# FLASH.net
KiCad netlist of a schematic drawn in Altium Designer
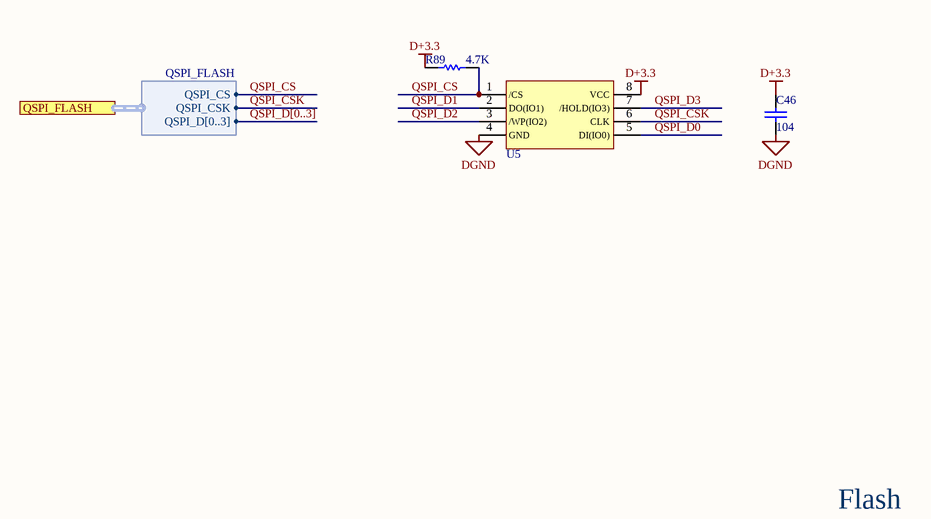
[diagram p0: FLASH.SchDoc]

(export (version "E")
  (design (tool "Eeschema 10.0.6"))
  (components
    (comp (ref "C46")
      (value "104")
      (footprint "C 0402_LL")
      (description "Capacitor")
      (fields (field (name "PUBLISHER") "Altium Limited"))
      (libsource (lib "Miscellaneous Devices") (part "Cap"))
    )
    (comp (ref "R89")
      (value "4.7K")
      (footprint "R 0603_L")
      (description "Resistor")
      (fields (field (name "PUBLISHER") "Altium Limited"))
      (libsource (lib "Miscellaneous Devices") (part "Res1"))
    )
    (comp (ref "U5")
      (value "W25Q128")
      (footprint "SOP8W_L")
      (libsource (lib "ZYNQ7010_add") (part "W25Q128"))
    )
  )
  (nets
    (net (code "2") (name "/QSPI_CS") (class "Default")
      (node (ref "R89") (pin "1") (pinfunction "1_1") (pintype "passive"))
      (node (ref "U5") (pin "1") (pinfunction "/CS_1") (pintype "passive"))
    )
    (net (code "3") (name "/QSPI_CSK") (class "Default")
      (node (ref "U5") (pin "6") (pinfunction "CLK_6") (pintype "passive"))
    )
    (net (code "4") (name "/QSPI_D0") (class "Default")
      (node (ref "U5") (pin "5") (pinfunction "DI(IO0)_5") (pintype "passive"))
    )
    (net (code "5") (name "/QSPI_D1") (class "Default")
      (node (ref "U5") (pin "2") (pinfunction "DO(IO1)_2") (pintype "passive"))
    )
    (net (code "6") (name "/QSPI_D2") (class "Default")
      (node (ref "U5") (pin "3") (pinfunction "/WP(IO2)_3") (pintype "passive"))
    )
    (net (code "7") (name "/QSPI_D3") (class "Default")
      (node (ref "U5") (pin "7") (pinfunction "/HOLD(IO3)_7") (pintype "passive"))
    )
    (net (code "10") (name "D+3.3") (class "Default")
      (node (ref "C46") (pin "2") (pinfunction "2_2") (pintype "passive"))
      (node (ref "R89") (pin "2") (pinfunction "2_2") (pintype "passive"))
      (node (ref "U5") (pin "8") (pinfunction "VCC_8") (pintype "passive"))
    )
    (net (code "11") (name "DGND") (class "Default")
      (node (ref "C46") (pin "1") (pinfunction "1_1") (pintype "passive"))
      (node (ref "U5") (pin "4") (pinfunction "GND_4") (pintype "passive"))
    )
  )
)
